# Sedna_Power_Board.net
KiCad netlist of a schematic drawn in EAGLE
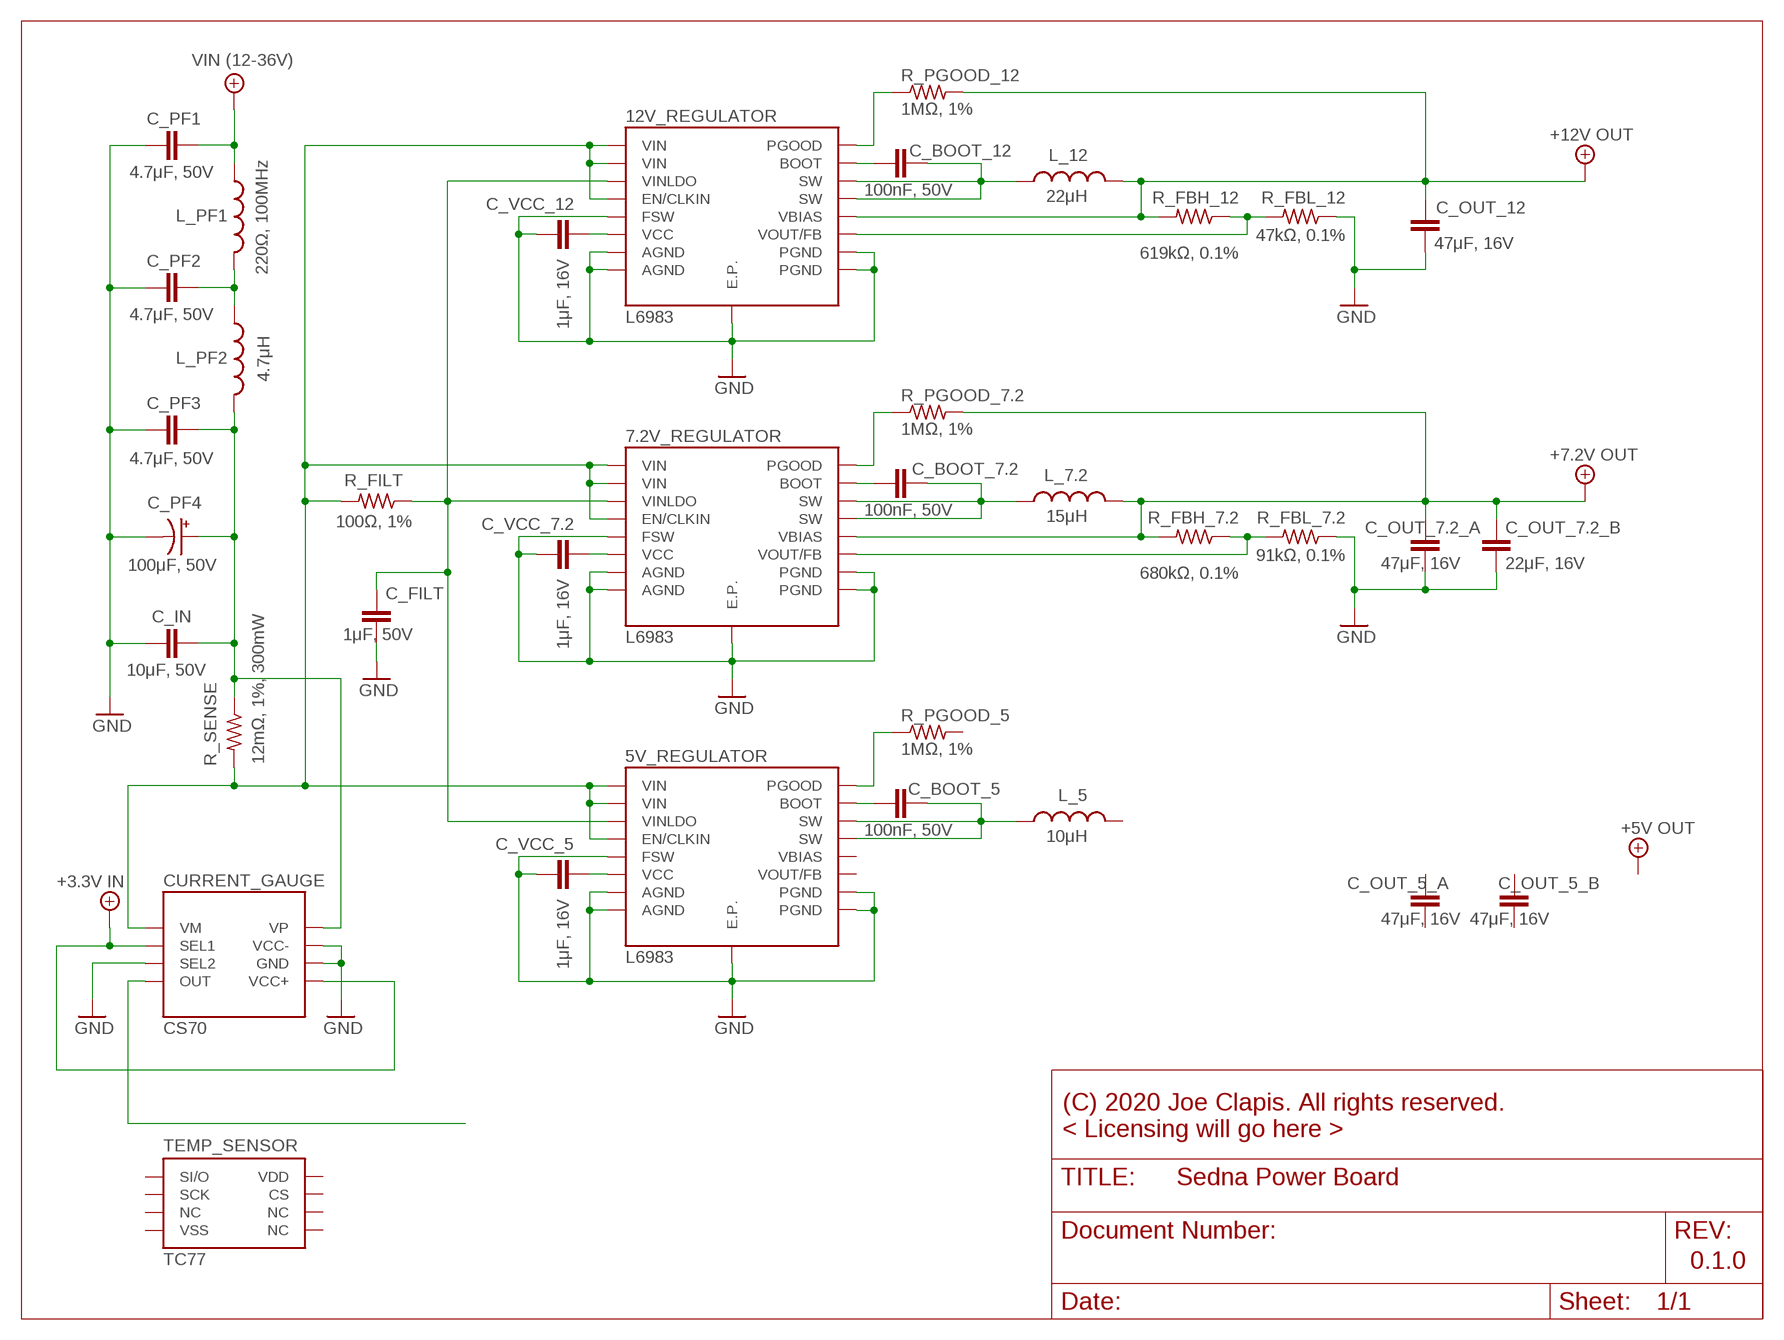
[diagram p0: schematic, sheet 1]

(export (version "E")
  (design (tool "Eeschema 10.0.6"))
  (components
    (comp (ref "5V_REGULATOR")
      (value "L6983")
      (footprint "eagle-import:L6983")
      (libsource (lib "eagle-import") (part "L6983"))
    )
    (comp (ref "7.2V_REGULATOR")
      (value "L6983")
      (footprint "eagle-import:L6983")
      (libsource (lib "eagle-import") (part "L6983"))
    )
    (comp (ref "12V_REGULATOR")
      (value "L6983")
      (footprint "eagle-import:L6983")
      (libsource (lib "eagle-import") (part "L6983"))
    )
    (comp (ref "CURRENT_GAUGE")
      (value "CS70")
      (footprint "eagle-import:TSSOP8")
      (libsource (lib "eagle-import") (part "CS70"))
    )
    (comp (ref "C_BOOT_5")
      (value "100nF, 50V")
      (footprint "eagle-import:C0603")
      (libsource (lib "eagle-import") (part "C-EUC0603"))
    )
    (comp (ref "C_BOOT_7.2")
      (value "100nF, 50V")
      (footprint "eagle-import:C0603")
      (libsource (lib "eagle-import") (part "C-EUC0603"))
    )
    (comp (ref "C_BOOT_12")
      (value "100nF, 50V")
      (footprint "eagle-import:C0603")
      (libsource (lib "eagle-import") (part "C-EUC0603"))
    )
    (comp (ref "C_FILT")
      (value "1μF, 50V")
      (footprint "eagle-import:C0805")
      (libsource (lib "eagle-import") (part "C-EUC0805"))
    )
    (comp (ref "C_IN")
      (value "10μF, 50V")
      (footprint "eagle-import:C1206")
      (libsource (lib "eagle-import") (part "C-EUC1206"))
    )
    (comp (ref "C_OUT_5_A")
      (value "47μF, 16V")
      (footprint "eagle-import:GRM_32")
      (libsource (lib "eagle-import") (part "GRM32"))
    )
    (comp (ref "C_OUT_5_B")
      (value "47μF, 16V")
      (footprint "eagle-import:GRM_32")
      (libsource (lib "eagle-import") (part "GRM32"))
    )
    (comp (ref "C_OUT_7.2_A")
      (value "47μF, 16V")
      (footprint "eagle-import:GRM_32")
      (libsource (lib "eagle-import") (part "GRM32"))
    )
    (comp (ref "C_OUT_7.2_B")
      (value "22μF, 16V")
      (footprint "eagle-import:GRM_31")
      (libsource (lib "eagle-import") (part "GRM31"))
    )
    (comp (ref "C_OUT_12")
      (value "47μF, 16V")
      (footprint "eagle-import:GRM_32")
      (libsource (lib "eagle-import") (part "GRM32"))
    )
    (comp (ref "C_PF1")
      (value "4.7μF, 50V")
      (footprint "eagle-import:C1206")
      (libsource (lib "eagle-import") (part "C-EUC1206"))
    )
    (comp (ref "C_PF2")
      (value "4.7μF, 50V")
      (footprint "eagle-import:C1206")
      (libsource (lib "eagle-import") (part "C-EUC1206"))
    )
    (comp (ref "C_PF3")
      (value "4.7μF, 50V")
      (footprint "eagle-import:C1206")
      (libsource (lib "eagle-import") (part "C-EUC1206"))
    )
    (comp (ref "C_PF4")
      (value "100μF, 50V")
      (footprint "eagle-import:PANASONIC_G")
      (libsource (lib "eagle-import") (part "CPOL-USG"))
    )
    (comp (ref "C_VCC_5")
      (value "1μF, 16V")
      (footprint "eagle-import:C0805")
      (libsource (lib "eagle-import") (part "C-EUC0805"))
    )
    (comp (ref "C_VCC_7.2")
      (value "1μF, 16V")
      (footprint "eagle-import:C0805")
      (libsource (lib "eagle-import") (part "C-EUC0805"))
    )
    (comp (ref "C_VCC_12")
      (value "1μF, 16V")
      (footprint "eagle-import:C0805")
      (libsource (lib "eagle-import") (part "C-EUC0805"))
    )
    (comp (ref "L_5")
      (value "10μH")
      (footprint "eagle-import:PA4343_FP2")
      (libsource (lib "eagle-import") (part "PA4343_FP2"))
    )
    (comp (ref "L_7.2")
      (value "15μH")
      (footprint "eagle-import:PA4343_FP2")
      (libsource (lib "eagle-import") (part "PA4343_FP2"))
    )
    (comp (ref "L_12")
      (value "22μH")
      (footprint "eagle-import:PA4343_FP2")
      (libsource (lib "eagle-import") (part "PA4343_FP2"))
    )
    (comp (ref "L_PF1")
      (value "220Ω, 100MHz")
      (footprint "eagle-import:L2012C")
      (libsource (lib "eagle-import") (part "L-USL2012C"))
    )
    (comp (ref "L_PF2")
      (value "4.7μH")
      (footprint "eagle-import:L2012C")
      (libsource (lib "eagle-import") (part "L-USL2012C"))
    )
    (comp (ref "R_FBH_7.2")
      (value "680kΩ, 0.1%")
      (footprint "eagle-import:R0805")
      (libsource (lib "eagle-import") (part "R-US_R0805"))
    )
    (comp (ref "R_FBH_12")
      (value "619kΩ, 0.1%")
      (footprint "eagle-import:R0805")
      (libsource (lib "eagle-import") (part "R-US_R0805"))
    )
    (comp (ref "R_FBL_7.2")
      (value "91kΩ, 0.1%")
      (footprint "eagle-import:R0805")
      (libsource (lib "eagle-import") (part "R-US_R0805"))
    )
    (comp (ref "R_FBL_12")
      (value "47kΩ, 0.1%")
      (footprint "eagle-import:R0805")
      (libsource (lib "eagle-import") (part "R-US_R0805"))
    )
    (comp (ref "R_FILT")
      (value "100Ω, 1%")
      (footprint "eagle-import:R0402")
      (libsource (lib "eagle-import") (part "R-US_R0402"))
    )
    (comp (ref "R_PGOOD_5")
      (value "1MΩ, 1%")
      (footprint "eagle-import:R0805")
      (libsource (lib "eagle-import") (part "R-US_R0805"))
    )
    (comp (ref "R_PGOOD_7.2")
      (value "1MΩ, 1%")
      (footprint "eagle-import:R0805")
      (libsource (lib "eagle-import") (part "R-US_R0805"))
    )
    (comp (ref "R_PGOOD_12")
      (value "1MΩ, 1%")
      (footprint "eagle-import:R0805")
      (libsource (lib "eagle-import") (part "R-US_R0805"))
    )
    (comp (ref "R_SENSE")
      (value "12mΩ, 1%, 300mW")
      (footprint "eagle-import:WSK1206")
      (libsource (lib "eagle-import") (part "WSK1206"))
    )
    (comp (ref "TEMP_SENSOR")
      (value "TC77")
      (footprint "eagle-import:SOIC8")
      (libsource (lib "eagle-import") (part "TC77"))
    )
  )
  (nets
    (net (code "2") (name "+12V OUT") (class "Default")
      (node (ref "12V_REGULATOR") (pin "6_VBIAS") (pinfunction "VBIAS_6_VBIAS") (pintype "input"))
      (node (ref "7.2V_REGULATOR") (pin "6_VBIAS") (pinfunction "VBIAS_6_VBIAS") (pintype "input"))
      (node (ref "CURRENT_GAUGE") (pin "2") (pinfunction "SEL1_2") (pintype "input"))
      (node (ref "CURRENT_GAUGE") (pin "5") (pinfunction "VCC+_5") (pintype "power_in"))
      (node (ref "C_OUT_12") (pin "P$1") (pinfunction "1_P$1") (pintype "passive"))
      (node (ref "C_OUT_7.2_A") (pin "P$1") (pinfunction "1_P$1") (pintype "passive"))
      (node (ref "C_OUT_7.2_B") (pin "P$1") (pinfunction "1_P$1") (pintype "passive"))
      (node (ref "C_PF1") (pin "2") (pinfunction "2_2") (pintype "passive"))
      (node (ref "L_12") (pin "2") (pinfunction "2_2") (pintype "passive"))
      (node (ref "L_7.2") (pin "2") (pinfunction "2_2") (pintype "passive"))
      (node (ref "L_PF1") (pin "1") (pinfunction "1_1") (pintype "passive"))
      (node (ref "R_FBH_12") (pin "2") (pinfunction "2_2") (pintype "passive"))
      (node (ref "R_FBH_7.2") (pin "2") (pinfunction "2_2") (pintype "passive"))
      (node (ref "R_PGOOD_12") (pin "2") (pinfunction "2_2") (pintype "passive"))
      (node (ref "R_PGOOD_7.2") (pin "2") (pinfunction "2_2") (pintype "passive"))
    )
    (net (code "3") (name "/VDD") (class "Default")
      (node (ref "TEMP_SENSOR") (pin "8") (pinfunction "VDD_8") (pintype "power_in"))
    )
    (net (code "4") (name "/VSS") (class "Default")
      (node (ref "TEMP_SENSOR") (pin "4") (pinfunction "VSS_4") (pintype "power_in"))
    )
    (net (code "5") (name "GND") (class "Default")
      (node (ref "12V_REGULATOR") (pin "10_AGND") (pinfunction "AGND_10_AGND") (pintype "power_in"))
      (node (ref "12V_REGULATOR") (pin "13_PGND") (pinfunction "PGND_13_PGND") (pintype "power_in"))
      (node (ref "12V_REGULATOR") (pin "16_PGND") (pinfunction "PGND_16_PGND") (pintype "power_in"))
      (node (ref "12V_REGULATOR") (pin "3_AGND") (pinfunction "AGND_3_AGND") (pintype "power_in"))
      (node (ref "12V_REGULATOR") (pin "8_FSW") (pinfunction "FSW_8_FSW") (pintype "output"))
      (node (ref "12V_REGULATOR") (pin "E.P.") (pinfunction "E.P._E.P.") (pintype "power_in"))
      (node (ref "5V_REGULATOR") (pin "10_AGND") (pinfunction "AGND_10_AGND") (pintype "power_in"))
      (node (ref "5V_REGULATOR") (pin "13_PGND") (pinfunction "PGND_13_PGND") (pintype "power_in"))
      (node (ref "5V_REGULATOR") (pin "16_PGND") (pinfunction "PGND_16_PGND") (pintype "power_in"))
      (node (ref "5V_REGULATOR") (pin "3_AGND") (pinfunction "AGND_3_AGND") (pintype "power_in"))
      (node (ref "5V_REGULATOR") (pin "8_FSW") (pinfunction "FSW_8_FSW") (pintype "output"))
      (node (ref "5V_REGULATOR") (pin "E.P.") (pinfunction "E.P._E.P.") (pintype "power_in"))
      (node (ref "7.2V_REGULATOR") (pin "10_AGND") (pinfunction "AGND_10_AGND") (pintype "power_in"))
      (node (ref "7.2V_REGULATOR") (pin "13_PGND") (pinfunction "PGND_13_PGND") (pintype "power_in"))
      (node (ref "7.2V_REGULATOR") (pin "16_PGND") (pinfunction "PGND_16_PGND") (pintype "power_in"))
      (node (ref "7.2V_REGULATOR") (pin "3_AGND") (pinfunction "AGND_3_AGND") (pintype "power_in"))
      (node (ref "7.2V_REGULATOR") (pin "8_FSW") (pinfunction "FSW_8_FSW") (pintype "output"))
      (node (ref "7.2V_REGULATOR") (pin "E.P.") (pinfunction "E.P._E.P.") (pintype "power_in"))
      (node (ref "CURRENT_GAUGE") (pin "3") (pinfunction "SEL2_3") (pintype "input"))
      (node (ref "CURRENT_GAUGE") (pin "6") (pinfunction "GND_6") (pintype "power_in"))
      (node (ref "CURRENT_GAUGE") (pin "7") (pinfunction "VCC-_7") (pintype "power_in"))
      (node (ref "C_FILT") (pin "1") (pinfunction "1_1") (pintype "passive"))
      (node (ref "C_IN") (pin "1") (pinfunction "1_1") (pintype "passive"))
      (node (ref "C_OUT_12") (pin "P$2") (pinfunction "2_P$2") (pintype "passive"))
      (node (ref "C_OUT_7.2_A") (pin "P$2") (pinfunction "2_P$2") (pintype "passive"))
      (node (ref "C_OUT_7.2_B") (pin "P$2") (pinfunction "2_P$2") (pintype "passive"))
      (node (ref "C_PF1") (pin "1") (pinfunction "1_1") (pintype "passive"))
      (node (ref "C_PF2") (pin "1") (pinfunction "1_1") (pintype "passive"))
      (node (ref "C_PF3") (pin "1") (pinfunction "1_1") (pintype "passive"))
      (node (ref "C_PF4") (pin "-") (pinfunction "-_-") (pintype "passive"))
      (node (ref "C_VCC_12") (pin "1") (pinfunction "1_1") (pintype "passive"))
      (node (ref "C_VCC_5") (pin "1") (pinfunction "1_1") (pintype "passive"))
      (node (ref "C_VCC_7.2") (pin "1") (pinfunction "1_1") (pintype "passive"))
      (node (ref "R_FBL_12") (pin "1") (pinfunction "1_1") (pintype "passive"))
      (node (ref "R_FBL_7.2") (pin "1") (pinfunction "1_1") (pintype "passive"))
    )
    (net (code "6") (name "Net-(5V_REGULATOR-BOOT)") (class "Default")
      (node (ref "5V_REGULATOR") (pin "11_BOOT") (pinfunction "BOOT_11_BOOT") (pintype "power_in"))
      (node (ref "C_BOOT_5") (pin "1") (pinfunction "1_1") (pintype "passive"))
    )
    (net (code "7") (name "Net-(5V_REGULATOR-PGOOD)") (class "Default")
      (node (ref "5V_REGULATOR") (pin "5_PGOOD") (pinfunction "PGOOD_5_PGOOD") (pintype "output"))
      (node (ref "R_PGOOD_5") (pin "1") (pinfunction "1_1") (pintype "passive"))
    )
    (net (code "8") (name "Net-(5V_REGULATOR-SW-Pad14_SW)") (class "Default")
      (node (ref "5V_REGULATOR") (pin "14_SW") (pinfunction "SW_14_SW") (pintype "power_in"))
      (node (ref "5V_REGULATOR") (pin "15_SW") (pinfunction "SW_15_SW") (pintype "power_in"))
      (node (ref "C_BOOT_5") (pin "2") (pinfunction "2_2") (pintype "passive"))
      (node (ref "L_5") (pin "1") (pinfunction "1_1") (pintype "passive"))
    )
    (net (code "9") (name "Net-(5V_REGULATOR-VCC)") (class "Default")
      (node (ref "5V_REGULATOR") (pin "9_VCC") (pinfunction "VCC_9_VCC") (pintype "power_in"))
      (node (ref "C_VCC_5") (pin "2") (pinfunction "2_2") (pintype "passive"))
    )
    (net (code "10") (name "Net-(7.2V_REGULATOR-BOOT)") (class "Default")
      (node (ref "7.2V_REGULATOR") (pin "11_BOOT") (pinfunction "BOOT_11_BOOT") (pintype "power_in"))
      (node (ref "C_BOOT_7.2") (pin "1") (pinfunction "1_1") (pintype "passive"))
    )
    (net (code "11") (name "Net-(7.2V_REGULATOR-PGOOD)") (class "Default")
      (node (ref "7.2V_REGULATOR") (pin "5_PGOOD") (pinfunction "PGOOD_5_PGOOD") (pintype "output"))
      (node (ref "R_PGOOD_7.2") (pin "1") (pinfunction "1_1") (pintype "passive"))
    )
    (net (code "12") (name "Net-(7.2V_REGULATOR-SW-Pad14_SW)") (class "Default")
      (node (ref "7.2V_REGULATOR") (pin "14_SW") (pinfunction "SW_14_SW") (pintype "power_in"))
      (node (ref "7.2V_REGULATOR") (pin "15_SW") (pinfunction "SW_15_SW") (pintype "power_in"))
      (node (ref "C_BOOT_7.2") (pin "2") (pinfunction "2_2") (pintype "passive"))
      (node (ref "L_7.2") (pin "1") (pinfunction "1_1") (pintype "passive"))
    )
    (net (code "13") (name "Net-(7.2V_REGULATOR-VCC)") (class "Default")
      (node (ref "7.2V_REGULATOR") (pin "9_VCC") (pinfunction "VCC_9_VCC") (pintype "power_in"))
      (node (ref "C_VCC_7.2") (pin "2") (pinfunction "2_2") (pintype "passive"))
    )
    (net (code "14") (name "Net-(7.2V_REGULATOR-VOUT{slash}FB)") (class "Default")
      (node (ref "7.2V_REGULATOR") (pin "7_FB/VOUT") (pinfunction "VOUT/FB_7_FB/VOUT") (pintype "input"))
      (node (ref "R_FBH_7.2") (pin "1") (pinfunction "1_1") (pintype "passive"))
      (node (ref "R_FBL_7.2") (pin "2") (pinfunction "2_2") (pintype "passive"))
    )
    (net (code "15") (name "Net-(12V_REGULATOR-BOOT)") (class "Default")
      (node (ref "12V_REGULATOR") (pin "11_BOOT") (pinfunction "BOOT_11_BOOT") (pintype "power_in"))
      (node (ref "C_BOOT_12") (pin "1") (pinfunction "1_1") (pintype "passive"))
    )
    (net (code "16") (name "Net-(12V_REGULATOR-EN{slash}CLKIN)") (class "Default")
      (node (ref "12V_REGULATOR") (pin "12_VIN") (pinfunction "VIN_12_VIN") (pintype "power_in"))
      (node (ref "12V_REGULATOR") (pin "1_VIN") (pinfunction "VIN_1_VIN") (pintype "power_in"))
      (node (ref "12V_REGULATOR") (pin "4_EN/CLKIN") (pinfunction "EN/CLKIN_4_EN/CLKIN") (pintype "input"))
      (node (ref "5V_REGULATOR") (pin "12_VIN") (pinfunction "VIN_12_VIN") (pintype "power_in"))
      (node (ref "5V_REGULATOR") (pin "1_VIN") (pinfunction "VIN_1_VIN") (pintype "power_in"))
      (node (ref "5V_REGULATOR") (pin "4_EN/CLKIN") (pinfunction "EN/CLKIN_4_EN/CLKIN") (pintype "input"))
      (node (ref "7.2V_REGULATOR") (pin "12_VIN") (pinfunction "VIN_12_VIN") (pintype "power_in"))
      (node (ref "7.2V_REGULATOR") (pin "1_VIN") (pinfunction "VIN_1_VIN") (pintype "power_in"))
      (node (ref "7.2V_REGULATOR") (pin "4_EN/CLKIN") (pinfunction "EN/CLKIN_4_EN/CLKIN") (pintype "input"))
      (node (ref "CURRENT_GAUGE") (pin "1") (pinfunction "VM_1") (pintype "input"))
      (node (ref "R_FILT") (pin "2") (pinfunction "2_2") (pintype "passive"))
      (node (ref "R_SENSE") (pin "P$3") (pinfunction "2_P$3") (pintype "passive"))
      (node (ref "R_SENSE") (pin "P$4") (pinfunction "2_P$4") (pintype "passive"))
    )
    (net (code "17") (name "Net-(12V_REGULATOR-PGOOD)") (class "Default")
      (node (ref "12V_REGULATOR") (pin "5_PGOOD") (pinfunction "PGOOD_5_PGOOD") (pintype "output"))
      (node (ref "R_PGOOD_12") (pin "1") (pinfunction "1_1") (pintype "passive"))
    )
    (net (code "18") (name "Net-(12V_REGULATOR-SW-Pad14_SW)") (class "Default")
      (node (ref "12V_REGULATOR") (pin "14_SW") (pinfunction "SW_14_SW") (pintype "power_in"))
      (node (ref "12V_REGULATOR") (pin "15_SW") (pinfunction "SW_15_SW") (pintype "power_in"))
      (node (ref "C_BOOT_12") (pin "2") (pinfunction "2_2") (pintype "passive"))
      (node (ref "L_12") (pin "1") (pinfunction "1_1") (pintype "passive"))
    )
    (net (code "19") (name "Net-(12V_REGULATOR-VCC)") (class "Default")
      (node (ref "12V_REGULATOR") (pin "9_VCC") (pinfunction "VCC_9_VCC") (pintype "power_in"))
      (node (ref "C_VCC_12") (pin "2") (pinfunction "2_2") (pintype "passive"))
    )
    (net (code "20") (name "Net-(12V_REGULATOR-VINLDO)") (class "Default")
      (node (ref "12V_REGULATOR") (pin "2_VINLDO") (pinfunction "VINLDO_2_VINLDO") (pintype "power_in"))
      (node (ref "5V_REGULATOR") (pin "2_VINLDO") (pinfunction "VINLDO_2_VINLDO") (pintype "power_in"))
      (node (ref "7.2V_REGULATOR") (pin "2_VINLDO") (pinfunction "VINLDO_2_VINLDO") (pintype "power_in"))
      (node (ref "C_FILT") (pin "2") (pinfunction "2_2") (pintype "passive"))
      (node (ref "R_FILT") (pin "1") (pinfunction "1_1") (pintype "passive"))
    )
    (net (code "21") (name "Net-(12V_REGULATOR-VOUT{slash}FB)") (class "Default")
      (node (ref "12V_REGULATOR") (pin "7_FB/VOUT") (pinfunction "VOUT/FB_7_FB/VOUT") (pintype "input"))
      (node (ref "R_FBH_12") (pin "1") (pinfunction "1_1") (pintype "passive"))
      (node (ref "R_FBL_12") (pin "2") (pinfunction "2_2") (pintype "passive"))
    )
    (net (code "22") (name "Net-(CURRENT_GAUGE-VP)") (class "Default")
      (node (ref "CURRENT_GAUGE") (pin "8") (pinfunction "VP_8") (pintype "input"))
      (node (ref "C_IN") (pin "2") (pinfunction "2_2") (pintype "passive"))
      (node (ref "C_PF3") (pin "2") (pinfunction "2_2") (pintype "passive"))
      (node (ref "C_PF4") (pin "+") (pinfunction "+_+") (pintype "passive"))
      (node (ref "L_PF2") (pin "2") (pinfunction "2_2") (pintype "passive"))
      (node (ref "R_SENSE") (pin "P$1") (pinfunction "1_P$1") (pintype "passive"))
      (node (ref "R_SENSE") (pin "P$2") (pinfunction "1_P$2") (pintype "passive"))
    )
    (net (code "23") (name "Net-(C_PF2-Pad2)") (class "Default")
      (node (ref "C_PF2") (pin "2") (pinfunction "2_2") (pintype "passive"))
      (node (ref "L_PF1") (pin "2") (pinfunction "2_2") (pintype "passive"))
      (node (ref "L_PF2") (pin "1") (pinfunction "1_1") (pintype "passive"))
    )
    (net (code "24") (name "unconnected-(5V_REGULATOR-VBIAS-Pad6_VBIAS)") (class "Default")
      (node (ref "5V_REGULATOR") (pin "6_VBIAS") (pinfunction "VBIAS_6_VBIAS") (pintype "input"))
    )
    (net (code "25") (name "unconnected-(5V_REGULATOR-VOUT{slash}FB-Pad7_FB{slash}VOUT)") (class "Default")
      (node (ref "5V_REGULATOR") (pin "7_FB/VOUT") (pinfunction "VOUT/FB_7_FB/VOUT") (pintype "input"))
    )
    (net (code "26") (name "unconnected-(CURRENT_GAUGE-OUT-Pad4)") (class "Default")
      (node (ref "CURRENT_GAUGE") (pin "4") (pinfunction "OUT_4") (pintype "output"))
    )
    (net (code "27") (name "unconnected-(C_OUT_5_A-1-PadP$1)") (class "Default")
      (node (ref "C_OUT_5_A") (pin "P$1") (pinfunction "1_P$1") (pintype "passive"))
    )
    (net (code "28") (name "unconnected-(C_OUT_5_A-2-PadP$2)") (class "Default")
      (node (ref "C_OUT_5_A") (pin "P$2") (pinfunction "2_P$2") (pintype "passive"))
    )
    (net (code "29") (name "unconnected-(C_OUT_5_B-1-PadP$1)") (class "Default")
      (node (ref "C_OUT_5_B") (pin "P$1") (pinfunction "1_P$1") (pintype "passive"))
    )
    (net (code "30") (name "unconnected-(C_OUT_5_B-2-PadP$2)") (class "Default")
      (node (ref "C_OUT_5_B") (pin "P$2") (pinfunction "2_P$2") (pintype "passive"))
    )
    (net (code "31") (name "unconnected-(L_5-Pad2)") (class "Default")
      (node (ref "L_5") (pin "2") (pinfunction "2_2") (pintype "passive"))
    )
    (net (code "32") (name "unconnected-(R_PGOOD_5-Pad2)") (class "Default")
      (node (ref "R_PGOOD_5") (pin "2") (pinfunction "2_2") (pintype "passive"))
    )
    (net (code "33") (name "unconnected-(TEMP_SENSOR-CS-Pad7)") (class "Default")
      (node (ref "TEMP_SENSOR") (pin "7") (pinfunction "CS_7") (pintype "input"))
    )
    (net (code "34") (name "unconnected-(TEMP_SENSOR-NC-Pad3)") (class "Default")
      (node (ref "TEMP_SENSOR") (pin "3") (pinfunction "NC_3") (pintype "no_connect"))
    )
    (net (code "35") (name "unconnected-(TEMP_SENSOR-NC-Pad5)") (class "Default")
      (node (ref "TEMP_SENSOR") (pin "5") (pinfunction "NC_5") (pintype "no_connect"))
    )
    (net (code "36") (name "unconnected-(TEMP_SENSOR-NC-Pad6)") (class "Default")
      (node (ref "TEMP_SENSOR") (pin "6") (pinfunction "NC_6") (pintype "no_connect"))
    )
    (net (code "37") (name "unconnected-(TEMP_SENSOR-SCK-Pad2)") (class "Default")
      (node (ref "TEMP_SENSOR") (pin "2") (pinfunction "SCK_2") (pintype "input"))
    )
    (net (code "38") (name "unconnected-(TEMP_SENSOR-SI{slash}O-Pad1)") (class "Default")
      (node (ref "TEMP_SENSOR") (pin "1") (pinfunction "SI/O_1") (pintype "output"))
    )
  )
)
